# Enlighten.net
KiCad netlist of a schematic drawn in EAGLE
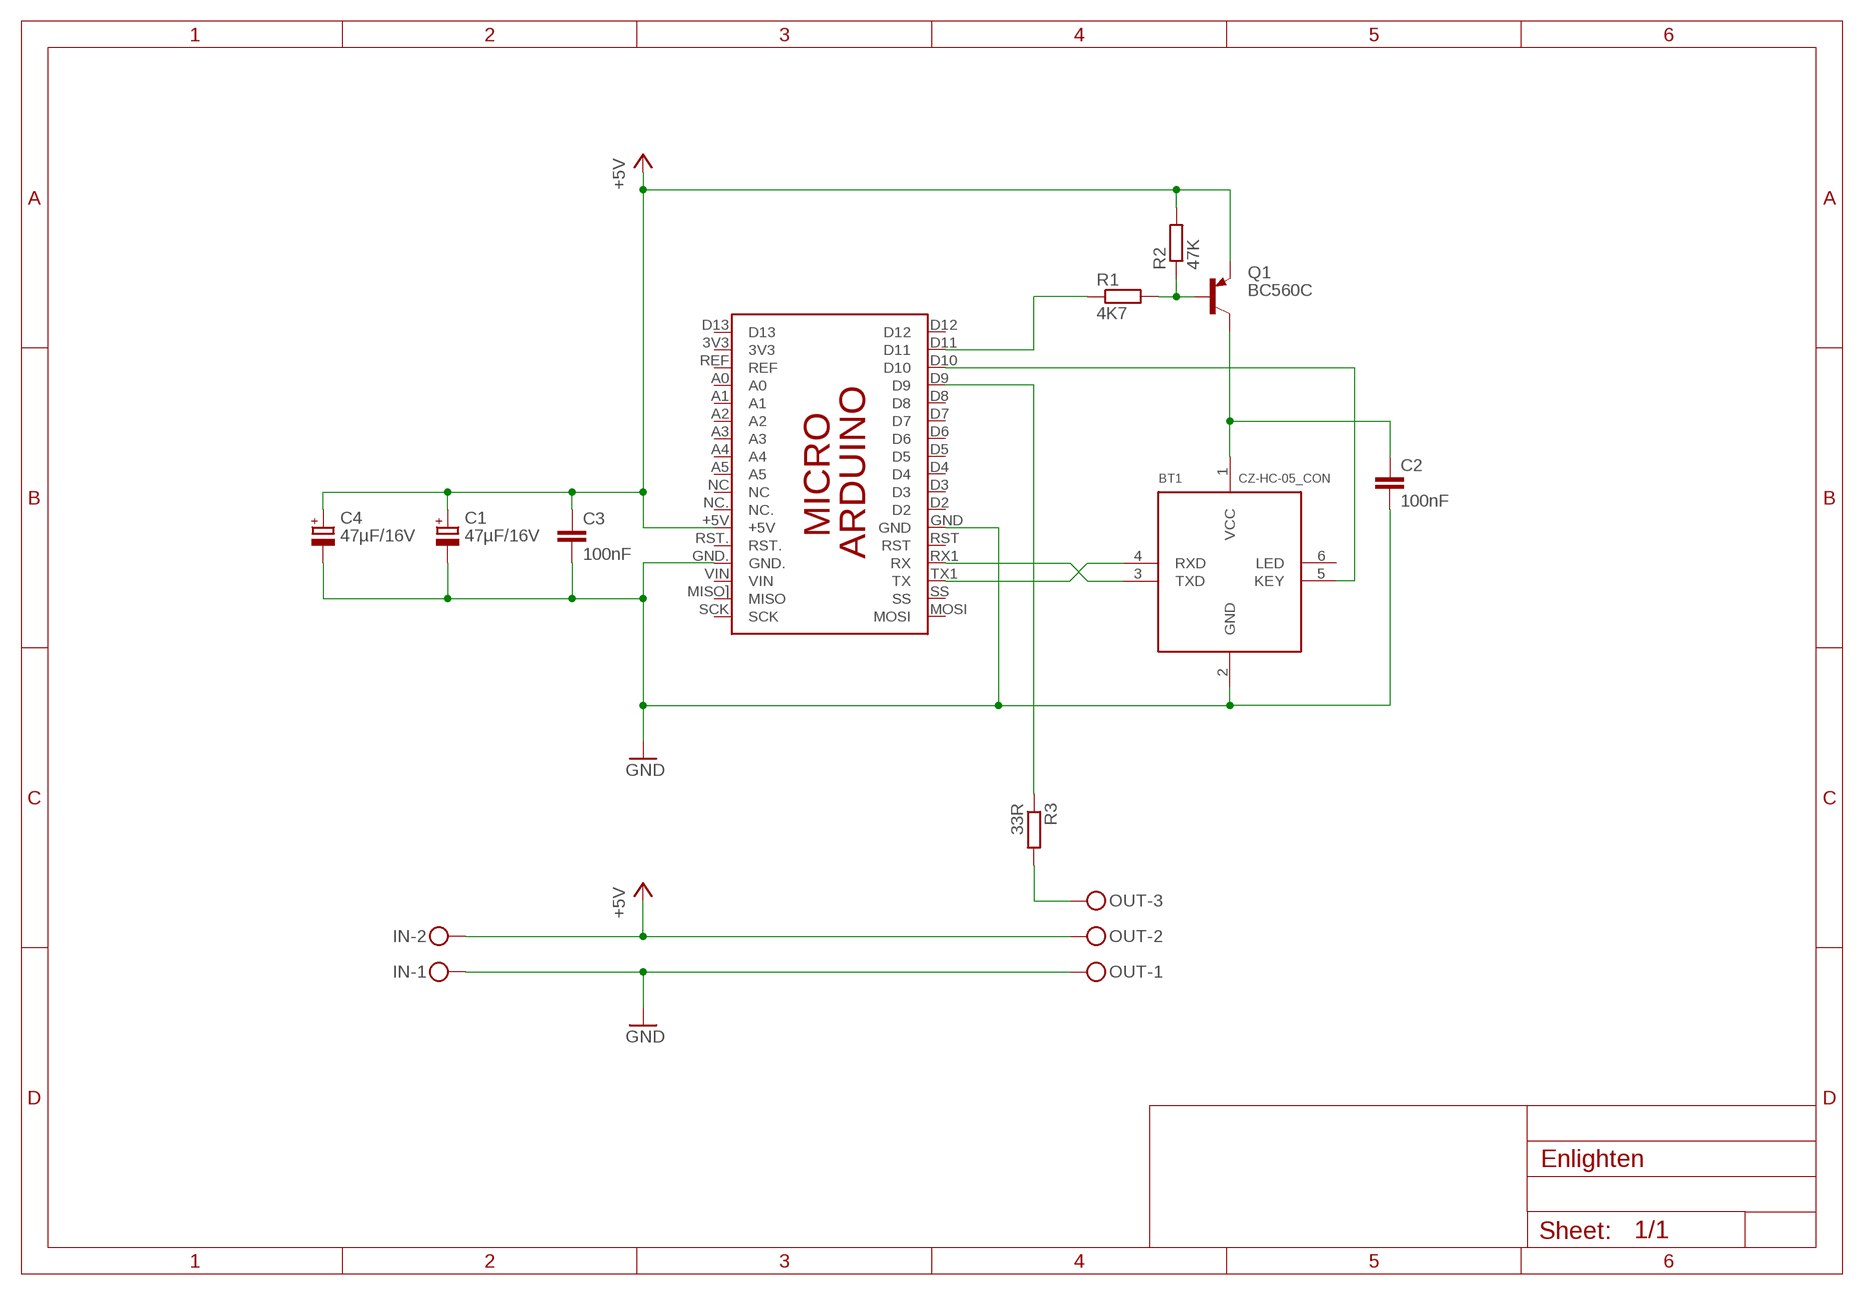
[diagram p0: schematic, sheet 1]

(export (version "E")
  (design (tool "Eeschema 10.0.6"))
  (components
    (comp (ref "BT1")
      (value "CZ-HC-05_CON")
      (footprint "eagle-import:CZ-HC-05_CON")
      (libsource (lib "eagle-import") (part "CZ-HC-05_CON"))
    )
    (comp (ref "C1")
      (value "47µF/16V")
      (footprint "eagle-import:E2-5")
      (libsource (lib "eagle-import") (part "CPOL-EUE2-5"))
    )
    (comp (ref "C2")
      (value "100nF")
      (footprint "eagle-import:C050-024X044")
      (libsource (lib "eagle-import") (part "C-EU050-024X044"))
    )
    (comp (ref "C3")
      (value "100nF")
      (footprint "eagle-import:C050-024X044")
      (libsource (lib "eagle-import") (part "C-EU050-024X044"))
    )
    (comp (ref "C4")
      (value "47µF/16V")
      (footprint "eagle-import:E2-5")
      (libsource (lib "eagle-import") (part "CPOL-EUE2-5"))
    )
    (comp (ref "IN")
      (value "MKDSN1,5/2-5,08")
      (footprint "eagle-import:MKDSN1,5_2-5,08")
      (libsource (lib "eagle-import") (part "MKDSN1,5/2-5,08"))
    )
    (comp (ref "OUT")
      (value "MKDSN1,5/3-5,08")
      (footprint "eagle-import:MKDSN1,5_3-5,08")
      (libsource (lib "eagle-import") (part "MKDSN1,5/3-5,08"))
    )
    (comp (ref "PCB1")
      (value "ARDUINO_MICRO")
      (footprint "eagle-import:ARDUINO_MICRO")
      (libsource (lib "eagle-import") (part "ARDUINO_MICRO"))
    )
    (comp (ref "Q1")
      (value "BC560C")
      (footprint "eagle-import:TO92-EBC")
      (libsource (lib "eagle-import") (part "BC560C"))
    )
    (comp (ref "R1")
      (value "4K7")
      (footprint "eagle-import:0207_10")
      (libsource (lib "eagle-import") (part "R-EU_0207/10"))
    )
    (comp (ref "R2")
      (value "47K")
      (footprint "eagle-import:0207_10")
      (libsource (lib "eagle-import") (part "R-EU_0207/10"))
    )
    (comp (ref "R3")
      (value "33R")
      (footprint "eagle-import:0207_10")
      (libsource (lib "eagle-import") (part "R-EU_0207/10"))
    )
  )
  (nets
    (net (code "1") (name "+5V") (class "Default")
      (node (ref "C1") (pin "+") (pinfunction "+_+") (pintype "passive"))
      (node (ref "C3") (pin "1") (pinfunction "1_1") (pintype "passive"))
      (node (ref "C4") (pin "+") (pinfunction "+_+") (pintype "passive"))
      (node (ref "IN") (pin "2") (pinfunction "KL_2") (pintype "passive"))
      (node (ref "OUT") (pin "2") (pinfunction "KL_2") (pintype "passive"))
      (node (ref "PCB1") (pin "+5V") (pinfunction "+5V_+5V") (pintype "bidirectional"))
      (node (ref "Q1") (pin "E") (pinfunction "E_E") (pintype "passive"))
      (node (ref "R2") (pin "2") (pinfunction "2_2") (pintype "passive"))
    )
    (net (code "2") (name "GND") (class "Default")
      (node (ref "BT1") (pin "2") (pinfunction "GND_2") (pintype "power_in"))
      (node (ref "C1") (pin "-") (pinfunction "-_-") (pintype "passive"))
      (node (ref "C2") (pin "2") (pinfunction "2_2") (pintype "passive"))
      (node (ref "C3") (pin "2") (pinfunction "2_2") (pintype "passive"))
      (node (ref "C4") (pin "-") (pinfunction "-_-") (pintype "passive"))
      (node (ref "IN") (pin "1") (pinfunction "KL_1") (pintype "passive"))
      (node (ref "OUT") (pin "1") (pinfunction "KL_1") (pintype "passive"))
      (node (ref "PCB1") (pin "GND") (pinfunction "GND_GND") (pintype "bidirectional"))
      (node (ref "PCB1") (pin "GND.") (pinfunction "GND._GND.") (pintype "bidirectional"))
    )
    (net (code "3") (name "Net-(BT1-KEY)") (class "Default")
      (node (ref "BT1") (pin "5") (pinfunction "KEY_5") (pintype "passive"))
      (node (ref "PCB1") (pin "D10") (pinfunction "D10_D10") (pintype "bidirectional"))
    )
    (net (code "4") (name "Net-(BT1-RXD)") (class "Default")
      (node (ref "BT1") (pin "4") (pinfunction "RXD_4") (pintype "input"))
      (node (ref "PCB1") (pin "TX1") (pinfunction "TX_TX1") (pintype "bidirectional"))
    )
    (net (code "5") (name "Net-(BT1-TXD)") (class "Default")
      (node (ref "BT1") (pin "3") (pinfunction "TXD_3") (pintype "output"))
      (node (ref "PCB1") (pin "RX1") (pinfunction "RX_RX1") (pintype "bidirectional"))
    )
    (net (code "6") (name "Net-(BT1-VCC)") (class "Default")
      (node (ref "BT1") (pin "1") (pinfunction "VCC_1") (pintype "power_in"))
      (node (ref "C2") (pin "1") (pinfunction "1_1") (pintype "passive"))
      (node (ref "Q1") (pin "C") (pinfunction "C_C") (pintype "passive"))
    )
    (net (code "7") (name "Net-(OUTC-KL)") (class "Default")
      (node (ref "OUT") (pin "3") (pinfunction "KL_3") (pintype "passive"))
      (node (ref "R3") (pin "2") (pinfunction "2_2") (pintype "passive"))
    )
    (net (code "8") (name "Net-(PCB1-PadD9)") (class "Default")
      (node (ref "PCB1") (pin "D9") (pinfunction "D9_D9") (pintype "bidirectional"))
      (node (ref "R3") (pin "1") (pinfunction "1_1") (pintype "passive"))
    )
    (net (code "9") (name "Net-(PCB1-PadD11)") (class "Default")
      (node (ref "PCB1") (pin "D11") (pinfunction "D11_D11") (pintype "bidirectional"))
      (node (ref "R1") (pin "1") (pinfunction "1_1") (pintype "passive"))
    )
    (net (code "10") (name "Net-(Q1-PadB)") (class "Default")
      (node (ref "Q1") (pin "B") (pinfunction "B_B") (pintype "passive"))
      (node (ref "R1") (pin "2") (pinfunction "2_2") (pintype "passive"))
      (node (ref "R2") (pin "1") (pinfunction "1_1") (pintype "passive"))
    )
    (net (code "11") (name "unconnected-(BT1-LED-Pad6)") (class "Default")
      (node (ref "BT1") (pin "6") (pinfunction "LED_6") (pintype "passive"))
    )
    (net (code "12") (name "unconnected-(PCB1-MISO-PadMISO])") (class "Default")
      (node (ref "PCB1") (pin "MISO]") (pinfunction "MISO_MISO]") (pintype "bidirectional"))
    )
    (net (code "13") (name "unconnected-(PCB1-Pad3V3)") (class "Default")
      (node (ref "PCB1") (pin "3V3") (pinfunction "3V3_3V3") (pintype "bidirectional"))
    )
    (net (code "14") (name "unconnected-(PCB1-PadA0)") (class "Default")
      (node (ref "PCB1") (pin "A0") (pinfunction "A0_A0") (pintype "bidirectional"))
    )
    (net (code "15") (name "unconnected-(PCB1-PadA1)") (class "Default")
      (node (ref "PCB1") (pin "A1") (pinfunction "A1_A1") (pintype "bidirectional"))
    )
    (net (code "16") (name "unconnected-(PCB1-PadA2)") (class "Default")
      (node (ref "PCB1") (pin "A2") (pinfunction "A2_A2") (pintype "bidirectional"))
    )
    (net (code "17") (name "unconnected-(PCB1-PadA3)") (class "Default")
      (node (ref "PCB1") (pin "A3") (pinfunction "A3_A3") (pintype "bidirectional"))
    )
    (net (code "18") (name "unconnected-(PCB1-PadA4)") (class "Default")
      (node (ref "PCB1") (pin "A4") (pinfunction "A4_A4") (pintype "bidirectional"))
    )
    (net (code "19") (name "unconnected-(PCB1-PadA5)") (class "Default")
      (node (ref "PCB1") (pin "A5") (pinfunction "A5_A5") (pintype "bidirectional"))
    )
    (net (code "20") (name "unconnected-(PCB1-PadD2)") (class "Default")
      (node (ref "PCB1") (pin "D2") (pinfunction "D2_D2") (pintype "bidirectional"))
    )
    (net (code "21") (name "unconnected-(PCB1-PadD3)") (class "Default")
      (node (ref "PCB1") (pin "D3") (pinfunction "D3_D3") (pintype "bidirectional"))
    )
    (net (code "22") (name "unconnected-(PCB1-PadD4)") (class "Default")
      (node (ref "PCB1") (pin "D4") (pinfunction "D4_D4") (pintype "bidirectional"))
    )
    (net (code "23") (name "unconnected-(PCB1-PadD5)") (class "Default")
      (node (ref "PCB1") (pin "D5") (pinfunction "D5_D5") (pintype "bidirectional"))
    )
    (net (code "24") (name "unconnected-(PCB1-PadD6)") (class "Default")
      (node (ref "PCB1") (pin "D6") (pinfunction "D6_D6") (pintype "bidirectional"))
    )
    (net (code "25") (name "unconnected-(PCB1-PadD7)") (class "Default")
      (node (ref "PCB1") (pin "D7") (pinfunction "D7_D7") (pintype "bidirectional"))
    )
    (net (code "26") (name "unconnected-(PCB1-PadD8)") (class "Default")
      (node (ref "PCB1") (pin "D8") (pinfunction "D8_D8") (pintype "bidirectional"))
    )
    (net (code "27") (name "unconnected-(PCB1-PadD12)") (class "Default")
      (node (ref "PCB1") (pin "D12") (pinfunction "D12_D12") (pintype "bidirectional"))
    )
    (net (code "28") (name "unconnected-(PCB1-PadD13)") (class "Default")
      (node (ref "PCB1") (pin "D13") (pinfunction "D13_D13") (pintype "bidirectional"))
    )
    (net (code "29") (name "unconnected-(PCB1-PadMOSI)") (class "Default")
      (node (ref "PCB1") (pin "MOSI") (pinfunction "MOSI_MOSI") (pintype "bidirectional"))
    )
    (net (code "30") (name "unconnected-(PCB1-PadNC)") (class "Default")
      (node (ref "PCB1") (pin "NC") (pinfunction "NC_NC") (pintype "bidirectional"))
    )
    (net (code "31") (name "unconnected-(PCB1-PadNC.)") (class "Default")
      (node (ref "PCB1") (pin "NC.") (pinfunction "NC._NC.") (pintype "bidirectional"))
    )
    (net (code "32") (name "unconnected-(PCB1-PadREF)") (class "Default")
      (node (ref "PCB1") (pin "REF") (pinfunction "REF_REF") (pintype "bidirectional"))
    )
    (net (code "33") (name "unconnected-(PCB1-PadRST)") (class "Default")
      (node (ref "PCB1") (pin "RST") (pinfunction "RST_RST") (pintype "bidirectional"))
    )
    (net (code "34") (name "unconnected-(PCB1-PadRST.)") (class "Default")
      (node (ref "PCB1") (pin "RST.") (pinfunction "RST._RST.") (pintype "bidirectional"))
    )
    (net (code "35") (name "unconnected-(PCB1-PadSCK)") (class "Default")
      (node (ref "PCB1") (pin "SCK") (pinfunction "SCK_SCK") (pintype "bidirectional"))
    )
    (net (code "36") (name "unconnected-(PCB1-PadSS)") (class "Default")
      (node (ref "PCB1") (pin "SS") (pinfunction "SS_SS") (pintype "bidirectional"))
    )
    (net (code "37") (name "unconnected-(PCB1-PadVIN)") (class "Default")
      (node (ref "PCB1") (pin "VIN") (pinfunction "VIN_VIN") (pintype "bidirectional"))
    )
  )
)
